# coronakiller_Zusatzplatine.net
KiCad netlist of a schematic drawn in EAGLE
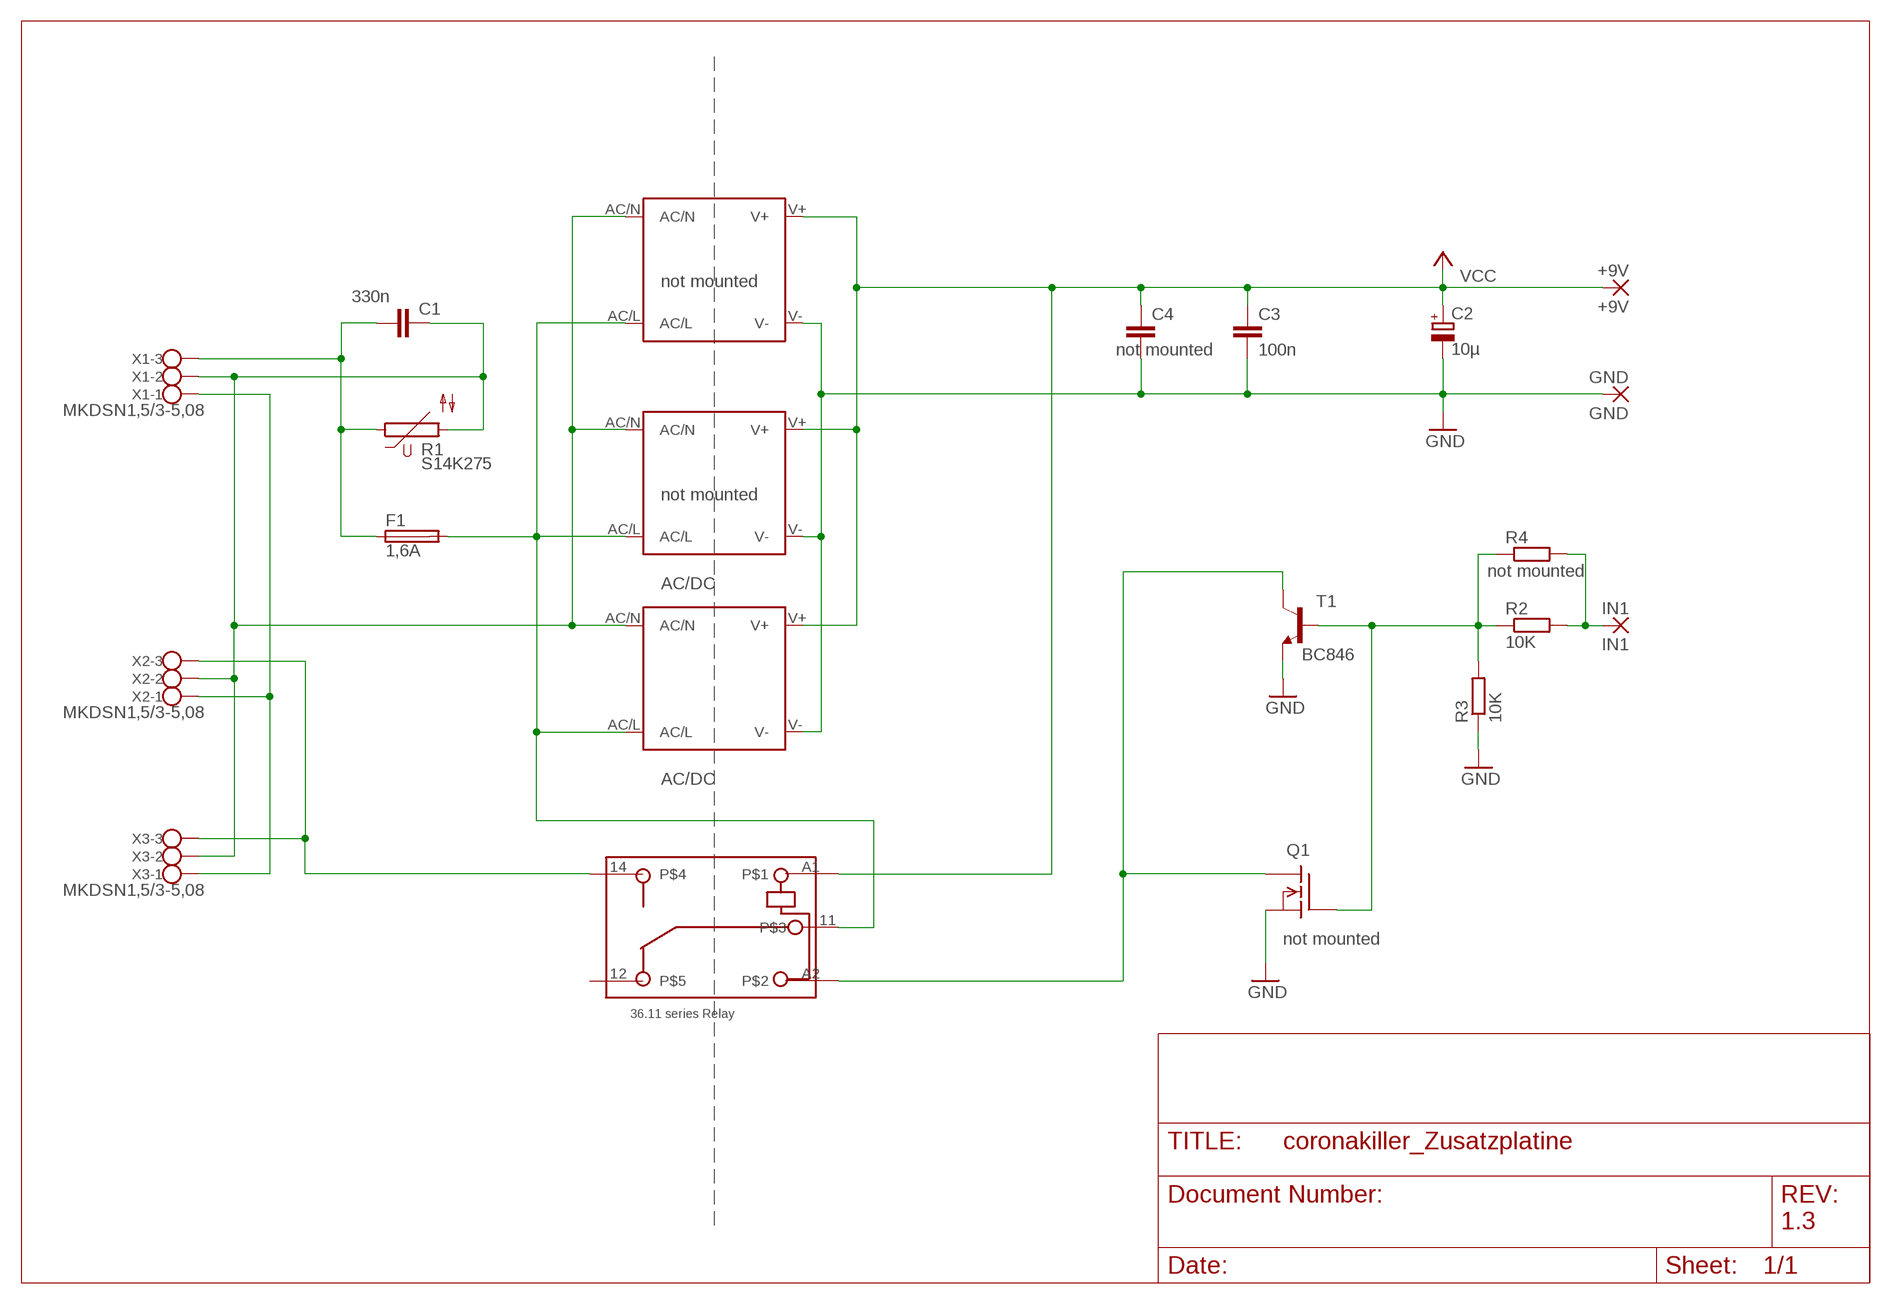
[diagram p0: schematic, sheet 1]

(export (version "E")
  (design (tool "Eeschema 10.0.6"))
  (components
    (comp (ref "+9V")
      (value "+9V")
      (footprint "eagle-import:2,54_1,0")
      (libsource (lib "eagle-import") (part "2,54/1,0"))
    )
    (comp (ref "AC/DC")
      (value "AC/DC")
      (footprint "eagle-import:IRM_03")
      (libsource (lib "eagle-import") (part "IRM_03"))
    )
    (comp (ref "C1")
      (value "330n")
      (footprint "eagle-import:C150-054X183")
      (libsource (lib "eagle-import") (part "C-EU150-054X183"))
    )
    (comp (ref "C2")
      (value "10µ")
      (footprint "eagle-import:E2,5-6")
      (libsource (lib "eagle-import") (part "CPOL-EUE2.5-6"))
    )
    (comp (ref "C3")
      (value "100n")
      (footprint "eagle-import:C0805")
      (libsource (lib "eagle-import") (part "C-EUC0805"))
    )
    (comp (ref "C4")
      (value "not mounted")
      (footprint "eagle-import:C025-040X050")
      (libsource (lib "eagle-import") (part "C-EU025-040X050"))
    )
    (comp (ref "F1")
      (value "1,6A")
      (footprint "eagle-import:SH22,5")
      (libsource (lib "eagle-import") (part "FUSESH22,5"))
    )
    (comp (ref "GND")
      (value "GND")
      (footprint "eagle-import:2,54_1,0")
      (libsource (lib "eagle-import") (part "2,54/1,0"))
    )
    (comp (ref "IN1")
      (value "IN1")
      (footprint "eagle-import:2,54_1,0")
      (libsource (lib "eagle-import") (part "2,54/1,0"))
    )
    (comp (ref "K1")
      (value "36.11")
      (footprint "eagle-import:36.11")
      (libsource (lib "eagle-import") (part "36.11"))
    )
    (comp (ref "Q1")
      (value "BSS101")
      (footprint "eagle-import:TO92")
      (libsource (lib "eagle-import") (part "BSS101"))
    )
    (comp (ref "R1")
      (value "S14K275")
      (footprint "eagle-import:S14K275")
      (libsource (lib "eagle-import") (part "S14K275"))
    )
    (comp (ref "R2")
      (value "10K")
      (footprint "eagle-import:R0805")
      (libsource (lib "eagle-import") (part "R-EU_R0805"))
    )
    (comp (ref "R3")
      (value "10K")
      (footprint "eagle-import:R0805")
      (libsource (lib "eagle-import") (part "R-EU_R0805"))
    )
    (comp (ref "R4")
      (value "not mounted")
      (footprint "eagle-import:V526-0")
      (libsource (lib "eagle-import") (part "R-EU_V526-0"))
    )
    (comp (ref "T1")
      (value "BC846")
      (footprint "eagle-import:SOT23")
      (libsource (lib "eagle-import") (part "BC846"))
    )
    (comp (ref "U$1")
      (value "not mounted")
      (footprint "eagle-import:IRM_01_02")
      (libsource (lib "eagle-import") (part "IRM_01/02IRM_01/02"))
    )
    (comp (ref "U$2")
      (value "not mounted")
      (footprint "eagle-import:IRM_01_02_SMD")
      (libsource (lib "eagle-import") (part "IRM_01/02_SMDIRM_01/02_SMD"))
    )
    (comp (ref "X1")
      (value "MKDSN1,5/3-5,08")
      (footprint "eagle-import:MKDSN1,5_3-5,08")
      (libsource (lib "eagle-import") (part "MKDSN1,5/3-5,08"))
    )
    (comp (ref "X2")
      (value "MKDSN1,5/3-5,08")
      (footprint "eagle-import:MKDSN1,5_3-5,08")
      (libsource (lib "eagle-import") (part "MKDSN1,5/3-5,08"))
    )
    (comp (ref "X3")
      (value "MKDSN1,5/3-5,08")
      (footprint "eagle-import:MKDSN1,5_3-5,08")
      (libsource (lib "eagle-import") (part "MKDSN1,5/3-5,08"))
    )
  )
  (nets
    (net (code "1") (name "GND") (class "Default")
      (node (ref "AC/DC") (pin "V-") (pinfunction "V-_V-") (pintype "output"))
      (node (ref "C2") (pin "-") (pinfunction "-_-") (pintype "passive"))
      (node (ref "C3") (pin "2") (pinfunction "2_2") (pintype "passive"))
      (node (ref "C4") (pin "2") (pinfunction "2_2") (pintype "passive"))
      (node (ref "GND") (pin "1") (pinfunction "P_1") (pintype "passive"))
      (node (ref "Q1") (pin "1") (pinfunction "S_1") (pintype "passive"))
      (node (ref "R3") (pin "1") (pinfunction "1_1") (pintype "passive"))
      (node (ref "T1") (pin "2") (pinfunction "E_2") (pintype "passive"))
      (node (ref "U$1") (pin "V-") (pinfunction "V-_V-") (pintype "output"))
      (node (ref "U$2") (pin "V-") (pinfunction "V-_V-") (pintype "output"))
    )
    (net (code "2") (name "Net-(IN1-P)") (class "Default")
      (node (ref "IN1") (pin "1") (pinfunction "P_1") (pintype "passive"))
      (node (ref "R2") (pin "2") (pinfunction "2_2") (pintype "passive"))
      (node (ref "R4") (pin "2") (pinfunction "2_2") (pintype "passive"))
    )
    (net (code "3") (name "Net-(K1-P$2)") (class "Default")
      (node (ref "K1") (pin "A2") (pinfunction "P$2_A2") (pintype "passive"))
      (node (ref "Q1") (pin "3") (pinfunction "D_3") (pintype "passive"))
      (node (ref "T1") (pin "3") (pinfunction "C_3") (pintype "passive"))
    )
    (net (code "4") (name "Net-(K1-P$3)") (class "Default")
      (node (ref "AC/DC") (pin "AC/L") (pinfunction "AC/L_AC/L") (pintype "input"))
      (node (ref "F1") (pin "2") (pinfunction "2_2") (pintype "passive"))
      (node (ref "K1") (pin "11") (pinfunction "P$3_11") (pintype "passive"))
      (node (ref "U$1") (pin "AC/L") (pinfunction "AC/L_AC/L") (pintype "input"))
      (node (ref "U$2") (pin "AC/L") (pinfunction "AC/L_AC/L") (pintype "input"))
    )
    (net (code "5") (name "Net-(K1-P$4)") (class "Default")
      (node (ref "K1") (pin "14") (pinfunction "P$4_14") (pintype "passive"))
      (node (ref "X2") (pin "3") (pinfunction "KL_3") (pintype "passive"))
      (node (ref "X3") (pin "3") (pinfunction "KL_3") (pintype "passive"))
    )
    (net (code "6") (name "Net-(Q1-G)") (class "Default")
      (node (ref "Q1") (pin "2") (pinfunction "G_2") (pintype "passive"))
      (node (ref "R2") (pin "1") (pinfunction "1_1") (pintype "passive"))
      (node (ref "R3") (pin "2") (pinfunction "2_2") (pintype "passive"))
      (node (ref "R4") (pin "1") (pinfunction "1_1") (pintype "passive"))
      (node (ref "T1") (pin "1") (pinfunction "B_1") (pintype "passive"))
    )
    (net (code "7") (name "Net-(X1A-KL)") (class "Default")
      (node (ref "X1") (pin "1") (pinfunction "KL_1") (pintype "passive"))
      (node (ref "X2") (pin "1") (pinfunction "KL_1") (pintype "passive"))
      (node (ref "X3") (pin "1") (pinfunction "KL_1") (pintype "passive"))
    )
    (net (code "8") (name "Net-(X1B-KL)") (class "Default")
      (node (ref "AC/DC") (pin "AC/N") (pinfunction "AC/N_AC/N") (pintype "input"))
      (node (ref "C1") (pin "1") (pinfunction "1_1") (pintype "passive"))
      (node (ref "R1") (pin "2") (pinfunction "2_2") (pintype "passive"))
      (node (ref "U$1") (pin "AC/N") (pinfunction "AC/N_AC/N") (pintype "input"))
      (node (ref "U$2") (pin "AC/N") (pinfunction "AC/N_AC/N") (pintype "input"))
      (node (ref "X1") (pin "2") (pinfunction "KL_2") (pintype "passive"))
      (node (ref "X2") (pin "2") (pinfunction "KL_2") (pintype "passive"))
      (node (ref "X3") (pin "2") (pinfunction "KL_2") (pintype "passive"))
    )
    (net (code "9") (name "Net-(X1C-KL)") (class "Default")
      (node (ref "C1") (pin "2") (pinfunction "2_2") (pintype "passive"))
      (node (ref "F1") (pin "1") (pinfunction "1_1") (pintype "passive"))
      (node (ref "R1") (pin "1") (pinfunction "1_1") (pintype "passive"))
      (node (ref "X1") (pin "3") (pinfunction "KL_3") (pintype "passive"))
    )
    (net (code "10") (name "VCC") (class "Default")
      (node (ref "+9V") (pin "1") (pinfunction "P_1") (pintype "passive"))
      (node (ref "AC/DC") (pin "V+") (pinfunction "V+_V+") (pintype "output"))
      (node (ref "C2") (pin "+") (pinfunction "+_+") (pintype "passive"))
      (node (ref "C3") (pin "1") (pinfunction "1_1") (pintype "passive"))
      (node (ref "C4") (pin "1") (pinfunction "1_1") (pintype "passive"))
      (node (ref "K1") (pin "A1") (pinfunction "P$1_A1") (pintype "passive"))
      (node (ref "U$1") (pin "V+") (pinfunction "V+_V+") (pintype "output"))
      (node (ref "U$2") (pin "V+") (pinfunction "V+_V+") (pintype "output"))
    )
    (net (code "11") (name "unconnected-(K1-P$5-Pad12)") (class "Default")
      (node (ref "K1") (pin "12") (pinfunction "P$5_12") (pintype "passive"))
    )
  )
)
